# Schematic.net
KiCad netlist of a schematic drawn in EasyEDA
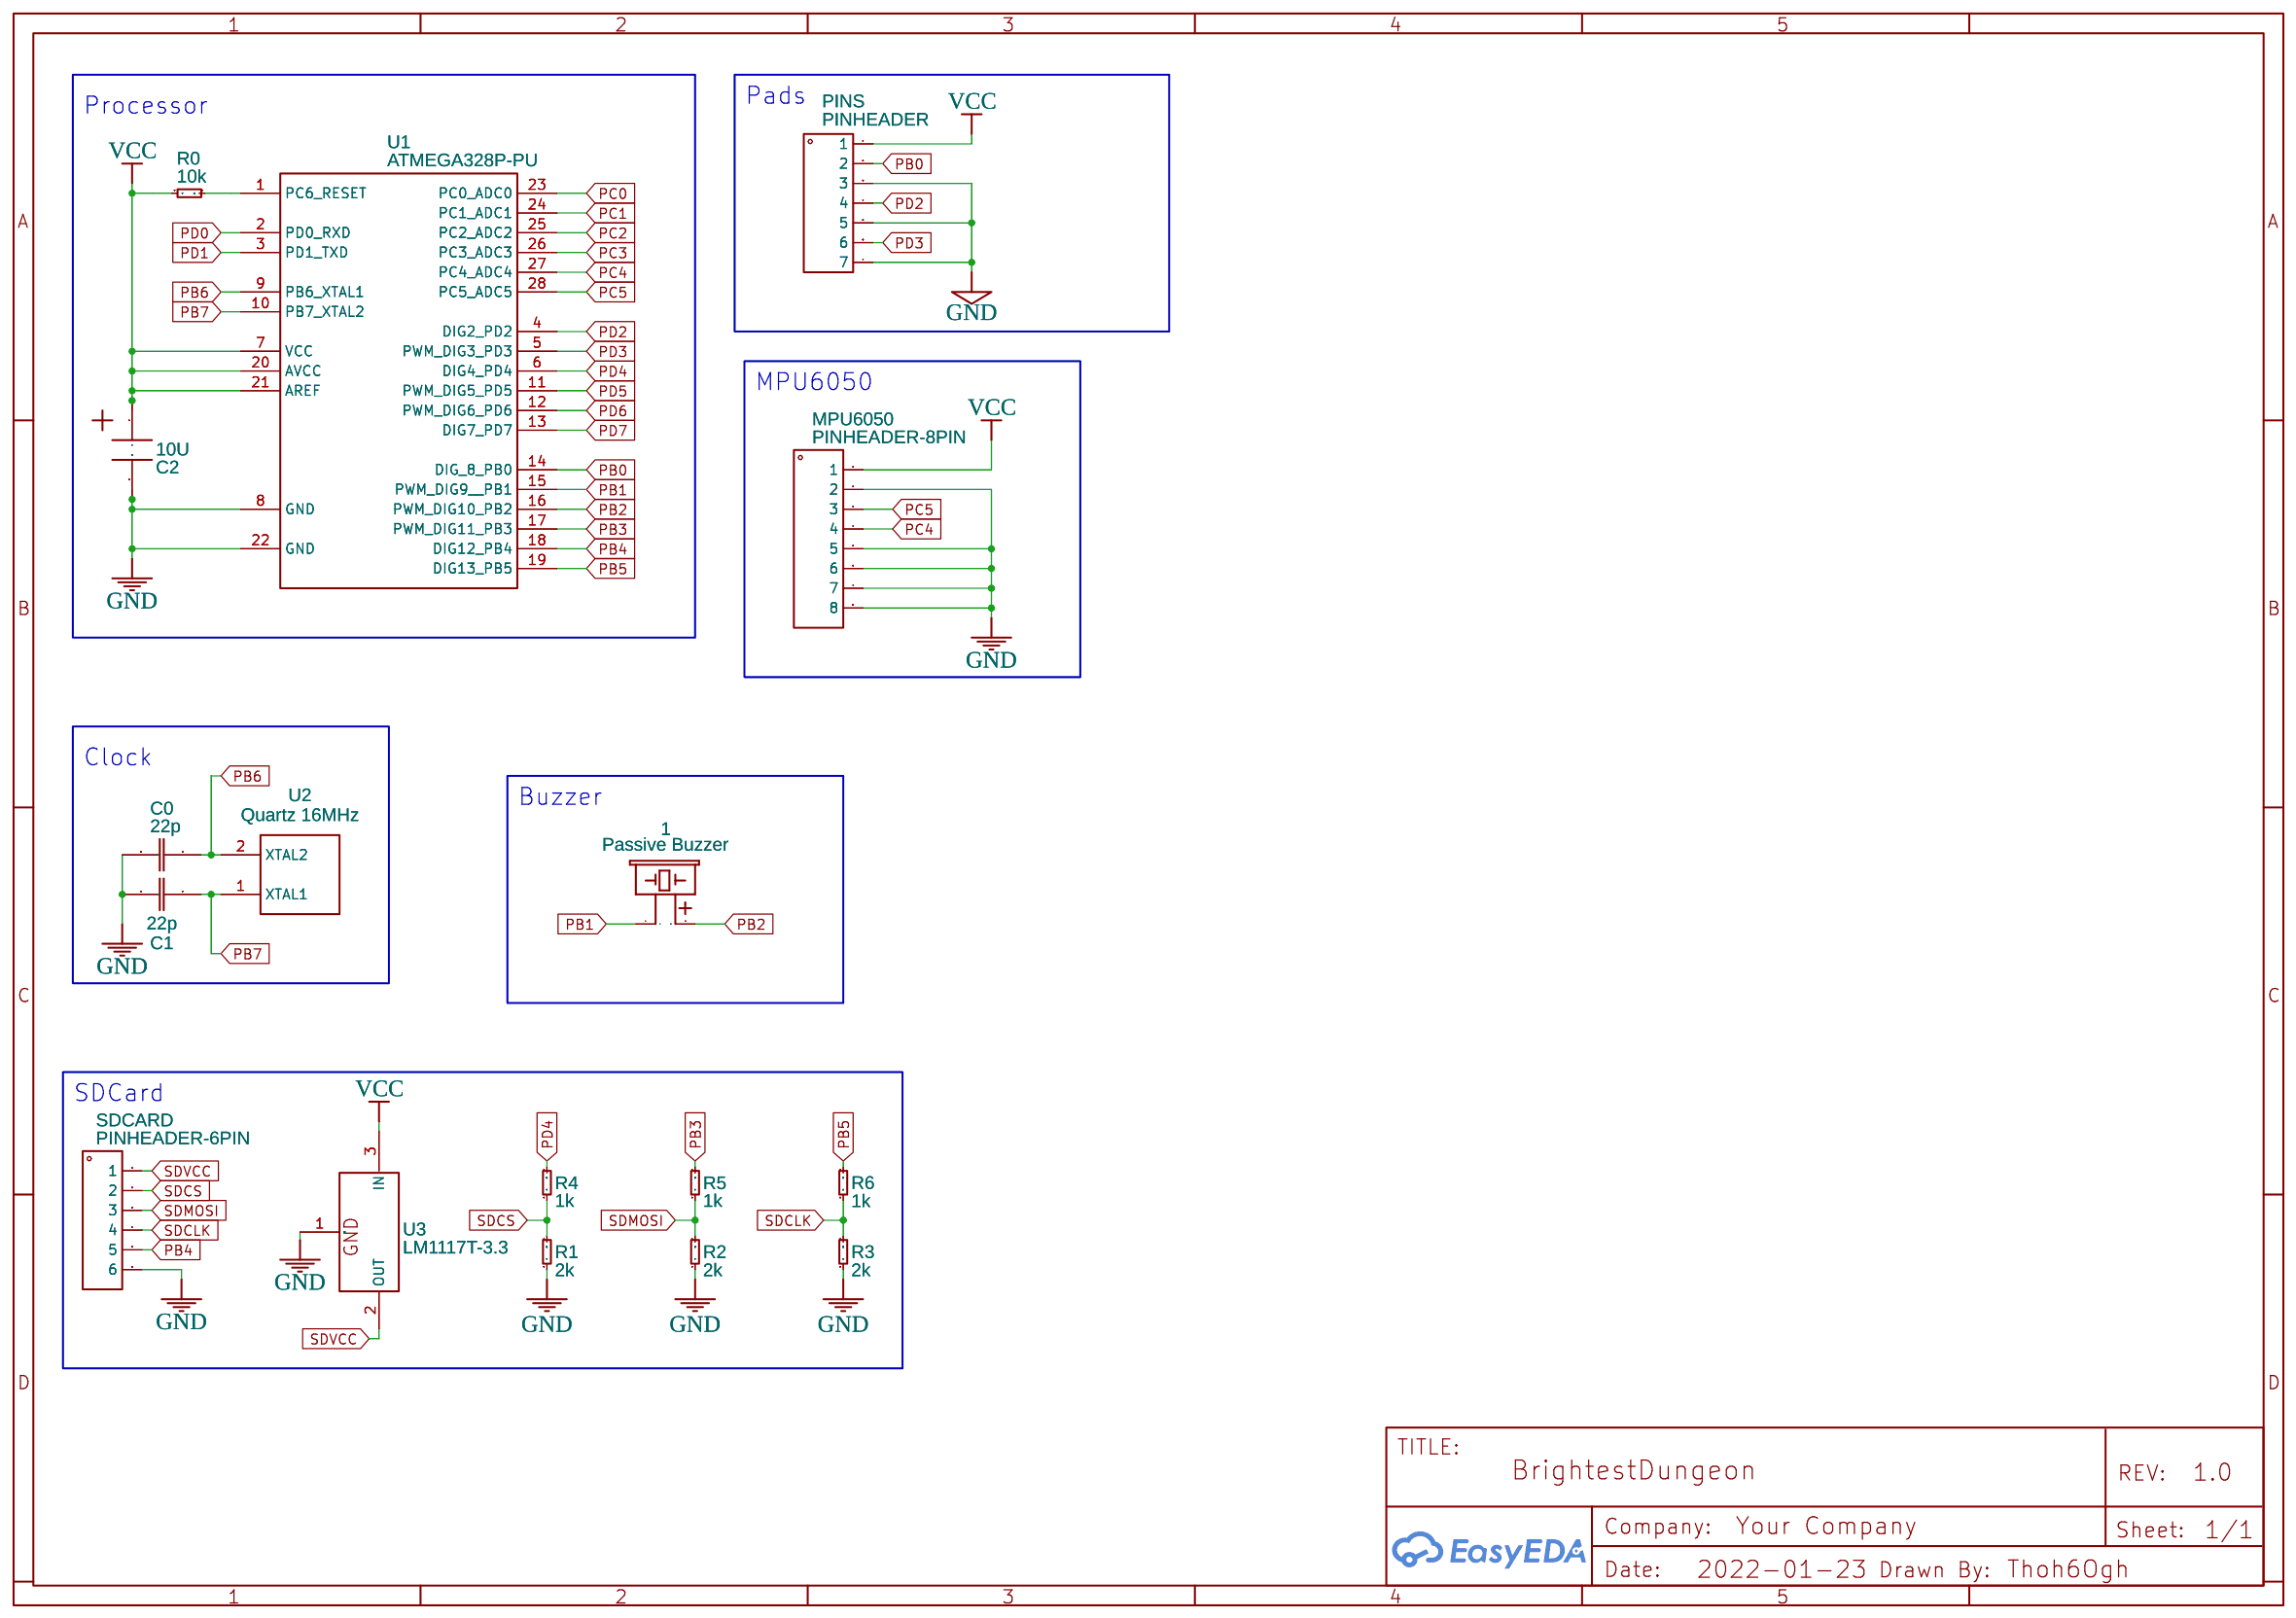
[diagram p0: schematic sheet]

(export (version "E")
  (design (tool "Eeschema 10.0.6"))
  (components
    (comp (ref "1") (value "Passive Buzzer") (libsource (lib "") (part "BUZZERBUZZER_PASSIVE_47")))
    (comp (ref "10U")
      (value "C2")
      (fields (field (name "BOM_Manufacturer Part") "C?"))
      (libsource (lib "") (part "C3"))
    )
    (comp (ref "C0")
      (value "22p")
      (fields (field (name "BOM_Supplier Part") "undefined"))
      (libsource (lib "") (part "1u"))
    )
    (comp (ref "C1")
      (value "22p")
      (fields (field (name "BOM_Supplier Part") "undefined"))
      (libsource (lib "") (part "1u"))
    )
    (comp (ref "MPU6050") (value "PINHEADER-8PIN") (libsource (lib "") (part "PINHEADER-8PIN")))
    (comp (ref "PINS") (value "PINHEADER") (libsource (lib "") (part "PINHEADER")))
    (comp (ref "R0")
      (value "10k")
      (fields
        (field (name "BOM_Manufacturer Part") "EWWR0003J250RT9")
        (field (name "BOM_Supplier Part") "C348861")
      )
      (libsource (lib "") (part "res_1"))
    )
    (comp (ref "R1")
      (value "2k")
      (fields
        (field (name "BOM_Manufacturer Part") "EWWR0003J250RT9")
        (field (name "BOM_Supplier Part") "C348861")
      )
      (libsource (lib "") (part "res"))
    )
    (comp (ref "R2")
      (value "2k")
      (fields
        (field (name "BOM_Manufacturer Part") "EWWR0003J250RT9")
        (field (name "BOM_Supplier Part") "C348861")
      )
      (libsource (lib "") (part "res"))
    )
    (comp (ref "R3")
      (value "2k")
      (fields
        (field (name "BOM_Manufacturer Part") "EWWR0003J250RT9")
        (field (name "BOM_Supplier Part") "C348861")
      )
      (libsource (lib "") (part "res"))
    )
    (comp (ref "R4")
      (value "1k")
      (fields
        (field (name "BOM_Manufacturer Part") "EWWR0003J250RT9")
        (field (name "BOM_Supplier Part") "C348861")
      )
      (libsource (lib "") (part "res"))
    )
    (comp (ref "R5")
      (value "1k")
      (fields
        (field (name "BOM_Manufacturer Part") "EWWR0003J250RT9")
        (field (name "BOM_Supplier Part") "C348861")
      )
      (libsource (lib "") (part "res"))
    )
    (comp (ref "R6")
      (value "1k")
      (fields
        (field (name "BOM_Manufacturer Part") "EWWR0003J250RT9")
        (field (name "BOM_Supplier Part") "C348861")
      )
      (libsource (lib "") (part "res"))
    )
    (comp (ref "SDCARD") (value "PINHEADER-6PIN") (libsource (lib "") (part "PINHEADER-6PIN")))
    (comp (ref "U1")
      (value "ATMEGA328P-PU")
      (fields (field (name "BOM_Supplier Part") "C33901"))
      (libsource (lib "") (part "ATMEGA328P-PU"))
    )
    (comp (ref "U2") (value "Quartz 16MHz") (libsource (lib "") (part "MyQuartz16MHz")))
    (comp (ref "U3")
      (value "LM1117T-3.3")
      (fields (field (name "BOM_Supplier Part") "C498321"))
      (libsource (lib "") (part "LM1117T-3.3"))
    )
  )
  (nets
    (net (code "1") (name "GND") (class "Default")
      (node (ref "10U") (pin "2") (pinfunction "2_2") (pintype "unspecified"))
      (node (ref "C0") (pin "1") (pinfunction "1_1") (pintype "unspecified"))
      (node (ref "C1") (pin "1") (pinfunction "1_1") (pintype "unspecified"))
      (node (ref "MPU6050") (pin "2") (pinfunction "2_2") (pintype "input"))
      (node (ref "MPU6050") (pin "5") (pinfunction "5_5") (pintype "input"))
      (node (ref "MPU6050") (pin "6") (pinfunction "6_6") (pintype "input"))
      (node (ref "MPU6050") (pin "7") (pinfunction "7_7") (pintype "input"))
      (node (ref "MPU6050") (pin "8") (pinfunction "8_8") (pintype "input"))
      (node (ref "PINS") (pin "3") (pinfunction "3_3") (pintype "input"))
      (node (ref "PINS") (pin "5") (pinfunction "5_5") (pintype "input"))
      (node (ref "PINS") (pin "7") (pinfunction "7_7") (pintype "input"))
      (node (ref "R1") (pin "2") (pinfunction "2_2") (pintype "unspecified"))
      (node (ref "R2") (pin "2") (pinfunction "2_2") (pintype "unspecified"))
      (node (ref "R3") (pin "2") (pinfunction "2_2") (pintype "unspecified"))
      (node (ref "SDCARD") (pin "6") (pinfunction "6_6") (pintype "input"))
      (node (ref "U1") (pin "22") (pinfunction "GND_22") (pintype "passive"))
      (node (ref "U1") (pin "8") (pinfunction "GND_8") (pintype "passive"))
      (node (ref "U3") (pin "1") (pinfunction "GND_1") (pintype "unspecified"))
    )
    (net (code "2") (name "Net-(R0-RES)") (class "Default")
      (node (ref "R0") (pin "1") (pinfunction "RES_1") (pintype "unspecified"))
      (node (ref "U1") (pin "1") (pinfunction "PC6_RESET_1") (pintype "bidirectional"))
    )
    (net (code "3") (name "PB0") (class "Default")
      (node (ref "PINS") (pin "2") (pinfunction "2_2") (pintype "input"))
      (node (ref "U1") (pin "14") (pinfunction "DIG_8_PB0_14") (pintype "bidirectional"))
    )
    (net (code "4") (name "PB1") (class "Default")
      (node (ref "1") (pin "-") (pinfunction "-_-") (pintype "bidirectional"))
      (node (ref "U1") (pin "15") (pinfunction "PWM_DIG9__PB1_15") (pintype "bidirectional"))
    )
    (net (code "5") (name "PB2") (class "Default")
      (node (ref "1") (pin "+") (pinfunction "+_+") (pintype "bidirectional"))
      (node (ref "U1") (pin "16") (pinfunction "PWM_DIG10_PB2_16") (pintype "bidirectional"))
    )
    (net (code "6") (name "PB3") (class "Default")
      (node (ref "R5") (pin "1") (pinfunction "RES_1") (pintype "unspecified"))
      (node (ref "U1") (pin "17") (pinfunction "PWM_DIG11_PB3_17") (pintype "bidirectional"))
    )
    (net (code "7") (name "PB4") (class "Default")
      (node (ref "SDCARD") (pin "5") (pinfunction "5_5") (pintype "input"))
      (node (ref "U1") (pin "18") (pinfunction "DIG12_PB4_18") (pintype "bidirectional"))
    )
    (net (code "8") (name "PB5") (class "Default")
      (node (ref "R6") (pin "1") (pinfunction "RES_1") (pintype "unspecified"))
      (node (ref "U1") (pin "19") (pinfunction "DIG13_PB5_19") (pintype "bidirectional"))
    )
    (net (code "9") (name "PB6") (class "Default")
      (node (ref "C0") (pin "2") (pinfunction "2_2") (pintype "unspecified"))
      (node (ref "U1") (pin "9") (pinfunction "PB6_XTAL1_9") (pintype "bidirectional"))
      (node (ref "U2") (pin "2") (pinfunction "XTAL2_2") (pintype "unspecified"))
    )
    (net (code "10") (name "PB7") (class "Default")
      (node (ref "C1") (pin "2") (pinfunction "2_2") (pintype "unspecified"))
      (node (ref "U1") (pin "10") (pinfunction "PB7_XTAL2_10") (pintype "bidirectional"))
      (node (ref "U2") (pin "1") (pinfunction "XTAL1_1") (pintype "unspecified"))
    )
    (net (code "11") (name "PC0") (class "Default")
      (node (ref "U1") (pin "23") (pinfunction "PC0_ADC0_23") (pintype "bidirectional"))
    )
    (net (code "12") (name "PC1") (class "Default")
      (node (ref "U1") (pin "24") (pinfunction "PC1_ADC1_24") (pintype "bidirectional"))
    )
    (net (code "13") (name "PC2") (class "Default")
      (node (ref "U1") (pin "25") (pinfunction "PC2_ADC2_25") (pintype "bidirectional"))
    )
    (net (code "14") (name "PC3") (class "Default")
      (node (ref "U1") (pin "26") (pinfunction "PC3_ADC3_26") (pintype "bidirectional"))
    )
    (net (code "15") (name "PC4") (class "Default")
      (node (ref "MPU6050") (pin "4") (pinfunction "4_4") (pintype "input"))
      (node (ref "U1") (pin "27") (pinfunction "PC4_ADC4_27") (pintype "bidirectional"))
    )
    (net (code "16") (name "PC5") (class "Default")
      (node (ref "MPU6050") (pin "3") (pinfunction "3_3") (pintype "input"))
      (node (ref "U1") (pin "28") (pinfunction "PC5_ADC5_28") (pintype "bidirectional"))
    )
    (net (code "17") (name "PD0") (class "Default")
      (node (ref "U1") (pin "2") (pinfunction "PD0_RXD_2") (pintype "bidirectional"))
    )
    (net (code "18") (name "PD1") (class "Default")
      (node (ref "U1") (pin "3") (pinfunction "PD1_TXD_3") (pintype "bidirectional"))
    )
    (net (code "19") (name "PD2") (class "Default")
      (node (ref "PINS") (pin "4") (pinfunction "4_4") (pintype "input"))
      (node (ref "U1") (pin "4") (pinfunction "DIG2_PD2_4") (pintype "bidirectional"))
    )
    (net (code "20") (name "PD3") (class "Default")
      (node (ref "PINS") (pin "6") (pinfunction "6_6") (pintype "input"))
      (node (ref "U1") (pin "5") (pinfunction "PWM_DIG3_PD3_5") (pintype "bidirectional"))
    )
    (net (code "21") (name "PD4") (class "Default")
      (node (ref "R4") (pin "1") (pinfunction "RES_1") (pintype "unspecified"))
      (node (ref "U1") (pin "6") (pinfunction "DIG4_PD4_6") (pintype "bidirectional"))
    )
    (net (code "22") (name "PD5") (class "Default")
      (node (ref "U1") (pin "11") (pinfunction "PWM_DIG5_PD5_11") (pintype "bidirectional"))
    )
    (net (code "23") (name "PD6") (class "Default")
      (node (ref "U1") (pin "12") (pinfunction "PWM_DIG6_PD6_12") (pintype "bidirectional"))
    )
    (net (code "24") (name "PD7") (class "Default")
      (node (ref "U1") (pin "13") (pinfunction "DIG7_PD7_13") (pintype "bidirectional"))
    )
    (net (code "25") (name "SDCLK") (class "Default")
      (node (ref "R3") (pin "1") (pinfunction "RES_1") (pintype "unspecified"))
      (node (ref "R6") (pin "2") (pinfunction "2_2") (pintype "unspecified"))
      (node (ref "SDCARD") (pin "4") (pinfunction "4_4") (pintype "input"))
    )
    (net (code "26") (name "SDCS") (class "Default")
      (node (ref "R1") (pin "1") (pinfunction "RES_1") (pintype "unspecified"))
      (node (ref "R4") (pin "2") (pinfunction "2_2") (pintype "unspecified"))
      (node (ref "SDCARD") (pin "2") (pinfunction "2_2") (pintype "input"))
    )
    (net (code "27") (name "SDMOSI") (class "Default")
      (node (ref "R2") (pin "1") (pinfunction "RES_1") (pintype "unspecified"))
      (node (ref "R5") (pin "2") (pinfunction "2_2") (pintype "unspecified"))
      (node (ref "SDCARD") (pin "3") (pinfunction "3_3") (pintype "input"))
    )
    (net (code "28") (name "SDVCC") (class "Default")
      (node (ref "SDCARD") (pin "1") (pinfunction "1_1") (pintype "input"))
      (node (ref "U3") (pin "2") (pinfunction "OUT_2") (pintype "unspecified"))
    )
    (net (code "29") (name "VCC") (class "Default")
      (node (ref "10U") (pin "1") (pinfunction "1_1") (pintype "unspecified"))
      (node (ref "MPU6050") (pin "1") (pinfunction "1_1") (pintype "input"))
      (node (ref "PINS") (pin "1") (pinfunction "1_1") (pintype "input"))
      (node (ref "R0") (pin "2") (pinfunction "2_2") (pintype "unspecified"))
      (node (ref "U1") (pin "20") (pinfunction "AVCC_20") (pintype "passive"))
      (node (ref "U1") (pin "21") (pinfunction "AREF_21") (pintype "passive"))
      (node (ref "U1") (pin "7") (pinfunction "VCC_7") (pintype "passive"))
      (node (ref "U3") (pin "3") (pinfunction "IN_3") (pintype "unspecified"))
    )
  )
)
